# design4B.net
KiCad netlist of a schematic drawn in EAGLE
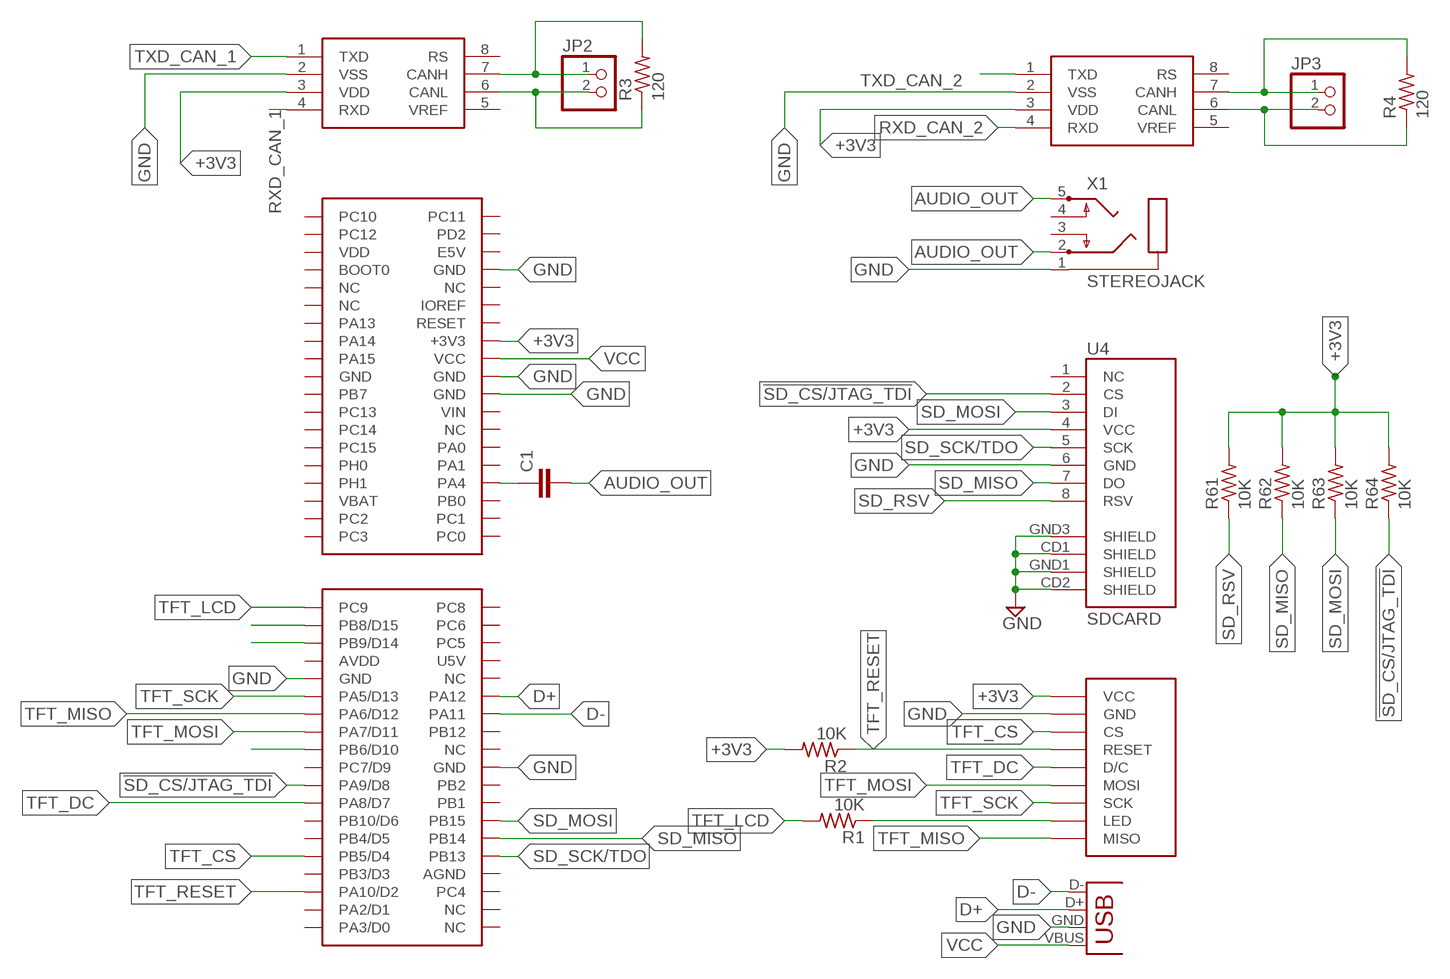
[diagram p0: schematic, sheet 1]

(export (version "E")
  (design (tool "Eeschema 10.0.6"))
  (components
    (comp (ref "C1")
      (value "CAP1206")
      (footprint "eagle-import:1206")
      (libsource (lib "eagle-import") (part "CAP1206"))
    )
    (comp (ref "J1")
      (value "SPI_TFT_DISPLAY")
      (footprint "eagle-import:SPI_DISPLAY")
      (libsource (lib "eagle-import") (part "SPI_TFT_DISPLAY"))
    )
    (comp (ref "JP1")
      (value "USB-A-H")
      (footprint "eagle-import:USB-A-H")
      (libsource (lib "eagle-import") (part "USB-A-H"))
    )
    (comp (ref "JP2")
      (value "HEADER-1X2")
      (footprint "eagle-import:1X02_OVAL")
      (libsource (lib "eagle-import") (part "HEADER-1X2"))
    )
    (comp (ref "JP3")
      (value "HEADER-1X2")
      (footprint "eagle-import:1X02_OVAL")
      (libsource (lib "eagle-import") (part "HEADER-1X2"))
    )
    (comp (ref "R1")
      (value "10K")
      (footprint "eagle-import:RLC_0603@1")
      (fields (field (name "MPN") "RMCF0603JT10K0"))
      (libsource (lib "eagle-import") (part "RESISTORRLC_0603"))
    )
    (comp (ref "R2")
      (value "10K")
      (footprint "eagle-import:RLC_0603@1")
      (fields (field (name "MPN") "RMCF0603JT10K0"))
      (libsource (lib "eagle-import") (part "RESISTORRLC_0603"))
    )
    (comp (ref "R3")
      (value "120")
      (footprint "eagle-import:RLC_0603@1")
      (fields (field (name "MPN") "RMCF0603JT10K0"))
      (libsource (lib "eagle-import") (part "RESISTORRLC_0603"))
    )
    (comp (ref "R4")
      (value "120")
      (footprint "eagle-import:RLC_0603@1")
      (fields (field (name "MPN") "RMCF0603JT10K0"))
      (libsource (lib "eagle-import") (part "RESISTORRLC_0603"))
    )
    (comp (ref "R61")
      (value "10K")
      (footprint "eagle-import:RLC_0603@1")
      (fields (field (name "MPN") "RMCF0603JT10K0"))
      (libsource (lib "eagle-import") (part "RESISTORRLC_0603"))
    )
    (comp (ref "R62")
      (value "10K")
      (footprint "eagle-import:RLC_0603@1")
      (fields (field (name "MPN") "RMCF0603JT10K0"))
      (libsource (lib "eagle-import") (part "RESISTORRLC_0603"))
    )
    (comp (ref "R63")
      (value "10K")
      (footprint "eagle-import:RLC_0603@1")
      (fields (field (name "MPN") "RMCF0603JT10K0"))
      (libsource (lib "eagle-import") (part "RESISTORRLC_0603"))
    )
    (comp (ref "R64")
      (value "10K")
      (footprint "eagle-import:RLC_0603@1")
      (fields (field (name "MPN") "RMCF0603JT10K0"))
      (libsource (lib "eagle-import") (part "RESISTORRLC_0603"))
    )
    (comp (ref "U$1")
      (value "MOPHOMOPHO_466RE")
      (footprint "eagle-import:MOPHO")
      (libsource (lib "eagle-import") (part "MOPHOMOPHO_466RE"))
    )
    (comp (ref "U1")
      (value "MCP2551")
      (footprint "eagle-import:SO08")
      (libsource (lib "eagle-import") (part "MCP2551"))
    )
    (comp (ref "U2")
      (value "MCP2551")
      (footprint "eagle-import:SO08")
      (libsource (lib "eagle-import") (part "MCP2551"))
    )
    (comp (ref "U4")
      (value "SDCARD")
      (footprint "eagle-import:MICRO-SD-SOCKET-PP")
      (libsource (lib "eagle-import") (part "USD-SOCKETNEW"))
    )
    (comp (ref "X1")
      (value "STEREOJACK")
      (footprint "eagle-import:STX3100")
      (libsource (lib "eagle-import") (part "STEREOJACK"))
    )
  )
  (nets
    (net (code "1") (name "+3V3") (class "Default")
      (node (ref "J1") (pin "VCC") (pinfunction "VCC_VCC") (pintype "power_in"))
      (node (ref "R2") (pin "2") (pinfunction "2_2") (pintype "passive"))
      (node (ref "R61") (pin "2") (pinfunction "2_2") (pintype "passive"))
      (node (ref "R62") (pin "2") (pinfunction "2_2") (pintype "passive"))
      (node (ref "R63") (pin "2") (pinfunction "2_2") (pintype "passive"))
      (node (ref "R64") (pin "2") (pinfunction "2_2") (pintype "passive"))
      (node (ref "U$1") (pin "P$16") (pinfunction "+3V3_P$16") (pintype "power_in"))
      (node (ref "U1") (pin "3") (pinfunction "VDD_3") (pintype "bidirectional"))
      (node (ref "U2") (pin "3") (pinfunction "VDD_3") (pintype "bidirectional"))
      (node (ref "U4") (pin "4") (pinfunction "VCC_4") (pintype "bidirectional"))
    )
    (net (code "2") (name "/AVDD") (class "Default")
      (node (ref "U$1") (pin "P$45") (pinfunction "AVDD_P$45") (pintype "power_in"))
    )
    (net (code "3") (name "/RXD_CAN_1") (class "Default")
      (node (ref "U2") (pin "4") (pinfunction "RXD_4") (pintype "bidirectional"))
    )
    (net (code "4") (name "/TXD_CAN_2") (class "Default")
      (node (ref "U1") (pin "1") (pinfunction "TXD_1") (pintype "bidirectional"))
    )
    (net (code "5") (name "/VBAT") (class "Default")
      (node (ref "U$1") (pin "P$33") (pinfunction "VBAT_P$33") (pintype "power_in"))
    )
    (net (code "6") (name "/VDD") (class "Default")
      (node (ref "U$1") (pin "P$5") (pinfunction "VDD_P$5") (pintype "power_in"))
    )
    (net (code "7") (name "/VIN") (class "Default")
      (node (ref "U$1") (pin "P$24") (pinfunction "VIN_P$24") (pintype "power_in"))
    )
    (net (code "8") (name "/~{SD_CS{slash}JTAG_TDI}") (class "Default")
      (node (ref "R64") (pin "1") (pinfunction "1_1") (pintype "passive"))
      (node (ref "U$1") (pin "P$59") (pinfunction "PA9/D8_P$59") (pintype "bidirectional"))
      (node (ref "U4") (pin "2") (pinfunction "CS_2") (pintype "bidirectional"))
    )
    (net (code "9") (name "AUDIO_OUT") (class "Default")
      (node (ref "C1") (pin "2") (pinfunction "2_2") (pintype "passive"))
      (node (ref "X1") (pin "2") (pinfunction "2_2") (pintype "passive"))
      (node (ref "X1") (pin "5") (pinfunction "5_5") (pintype "passive"))
    )
    (net (code "10") (name "D+") (class "Default")
      (node (ref "JP1") (pin "D+") (pinfunction "D-_D+") (pintype "bidirectional"))
      (node (ref "U$1") (pin "P$50") (pinfunction "PA12_P$50") (pintype "bidirectional"))
    )
    (net (code "11") (name "D-") (class "Default")
      (node (ref "JP1") (pin "D-") (pinfunction "D+_D-") (pintype "bidirectional"))
      (node (ref "U$1") (pin "P$52") (pinfunction "PA11_P$52") (pintype "bidirectional"))
    )
    (net (code "12") (name "GND") (class "Default")
      (node (ref "J1") (pin "GND") (pinfunction "GND_GND") (pintype "power_in"))
      (node (ref "JP1") (pin "GND") (pinfunction "VBUS_GND") (pintype "bidirectional"))
      (node (ref "U$1") (pin "P$20") (pinfunction "GND_P$20") (pintype "bidirectional"))
      (node (ref "U$1") (pin "P$22") (pinfunction "GND_P$22") (pintype "bidirectional"))
      (node (ref "U$1") (pin "P$47") (pinfunction "GND_P$47") (pintype "bidirectional"))
      (node (ref "U$1") (pin "P$58") (pinfunction "GND_P$58") (pintype "bidirectional"))
      (node (ref "U$1") (pin "P$8") (pinfunction "GND_P$8") (pintype "bidirectional"))
      (node (ref "U1") (pin "2") (pinfunction "VSS_2") (pintype "bidirectional"))
      (node (ref "U2") (pin "2") (pinfunction "VSS_2") (pintype "bidirectional"))
      (node (ref "U4") (pin "6") (pinfunction "GND_6") (pintype "bidirectional"))
      (node (ref "U4") (pin "CD1") (pinfunction "SHIELD_CD1") (pintype "bidirectional"))
      (node (ref "U4") (pin "CD2") (pinfunction "SHIELD_CD2") (pintype "bidirectional"))
      (node (ref "U4") (pin "GND1") (pinfunction "SHIELD_GND1") (pintype "bidirectional"))
      (node (ref "U4") (pin "GND3") (pinfunction "SHIELD_GND3") (pintype "bidirectional"))
      (node (ref "X1") (pin "1") (pinfunction "1_1") (pintype "passive"))
    )
    (net (code "13") (name "Net-(J1-PadLED)") (class "Default")
      (node (ref "J1") (pin "LED") (pinfunction "LED_LED") (pintype "bidirectional"))
      (node (ref "R1") (pin "1") (pinfunction "1_1") (pintype "passive"))
    )
    (net (code "14") (name "Net-(U$1-PA4)") (class "Default")
      (node (ref "C1") (pin "1") (pinfunction "1_1") (pintype "passive"))
      (node (ref "U$1") (pin "P$32") (pinfunction "PA4_P$32") (pintype "bidirectional"))
    )
    (net (code "15") (name "Net-(U1-CANH)") (class "Default")
      (node (ref "JP3") (pin "1") (pinfunction "1_1") (pintype "passive"))
      (node (ref "R4") (pin "2") (pinfunction "2_2") (pintype "passive"))
      (node (ref "U1") (pin "7") (pinfunction "CANH_7") (pintype "bidirectional"))
    )
    (net (code "16") (name "Net-(U1-CANL)") (class "Default")
      (node (ref "JP3") (pin "2") (pinfunction "2_2") (pintype "passive"))
      (node (ref "R4") (pin "1") (pinfunction "1_1") (pintype "passive"))
      (node (ref "U1") (pin "6") (pinfunction "CANL_6") (pintype "bidirectional"))
    )
    (net (code "17") (name "Net-(U2-CANH)") (class "Default")
      (node (ref "JP2") (pin "1") (pinfunction "1_1") (pintype "passive"))
      (node (ref "R3") (pin "2") (pinfunction "2_2") (pintype "passive"))
      (node (ref "U2") (pin "7") (pinfunction "CANH_7") (pintype "bidirectional"))
    )
    (net (code "18") (name "Net-(U2-CANL)") (class "Default")
      (node (ref "JP2") (pin "2") (pinfunction "2_2") (pintype "passive"))
      (node (ref "R3") (pin "1") (pinfunction "1_1") (pintype "passive"))
      (node (ref "U2") (pin "6") (pinfunction "CANL_6") (pintype "bidirectional"))
    )
    (net (code "19") (name "RXD_CAN_2") (class "Default")
      (node (ref "U1") (pin "4") (pinfunction "RXD_4") (pintype "bidirectional"))
    )
    (net (code "20") (name "SD_MISO") (class "Default")
      (node (ref "R62") (pin "1") (pinfunction "1_1") (pintype "passive"))
      (node (ref "U$1") (pin "P$66") (pinfunction "PB14_P$66") (pintype "bidirectional"))
      (node (ref "U4") (pin "7") (pinfunction "DO_7") (pintype "bidirectional"))
    )
    (net (code "21") (name "SD_MOSI") (class "Default")
      (node (ref "R63") (pin "1") (pinfunction "1_1") (pintype "passive"))
      (node (ref "U$1") (pin "P$64") (pinfunction "PB15_P$64") (pintype "bidirectional"))
      (node (ref "U4") (pin "3") (pinfunction "DI_3") (pintype "bidirectional"))
    )
    (net (code "22") (name "SD_RSV") (class "Default")
      (node (ref "R61") (pin "1") (pinfunction "1_1") (pintype "passive"))
      (node (ref "U4") (pin "8") (pinfunction "RSV_8") (pintype "bidirectional"))
    )
    (net (code "23") (name "SD_SCK{slash}TDO") (class "Default")
      (node (ref "U$1") (pin "P$68") (pinfunction "PB13_P$68") (pintype "bidirectional"))
      (node (ref "U4") (pin "5") (pinfunction "SCK_5") (pintype "bidirectional"))
    )
    (net (code "24") (name "TFT_CS") (class "Default")
      (node (ref "J1") (pin "CS") (pinfunction "CS_CS") (pintype "bidirectional"))
      (node (ref "U$1") (pin "P$67") (pinfunction "PB5/D4_P$67") (pintype "bidirectional"))
    )
    (net (code "25") (name "TFT_DC") (class "Default")
      (node (ref "J1") (pin "D/C") (pinfunction "D/C_D/C") (pintype "bidirectional"))
      (node (ref "U$1") (pin "P$61") (pinfunction "PA8/D7_P$61") (pintype "bidirectional"))
    )
    (net (code "26") (name "TFT_LCD") (class "Default")
      (node (ref "R1") (pin "2") (pinfunction "2_2") (pintype "passive"))
      (node (ref "U$1") (pin "P$39") (pinfunction "PC9_P$39") (pintype "bidirectional"))
    )
    (net (code "27") (name "TFT_MISO") (class "Default")
      (node (ref "J1") (pin "MISO") (pinfunction "MISO_MISO") (pintype "bidirectional"))
      (node (ref "U$1") (pin "P$51") (pinfunction "PA6/D12_P$51") (pintype "bidirectional"))
    )
    (net (code "28") (name "TFT_MOSI") (class "Default")
      (node (ref "J1") (pin "MOSI") (pinfunction "MOSI_MOSI") (pintype "bidirectional"))
      (node (ref "U$1") (pin "P$53") (pinfunction "PA7/D11_P$53") (pintype "bidirectional"))
    )
    (net (code "29") (name "TFT_RESET") (class "Default")
      (node (ref "J1") (pin "RESET") (pinfunction "RESET_RESET") (pintype "bidirectional"))
      (node (ref "R2") (pin "1") (pinfunction "1_1") (pintype "passive"))
      (node (ref "U$1") (pin "P$71") (pinfunction "PA10/D2_P$71") (pintype "bidirectional"))
    )
    (net (code "30") (name "TFT_SCK") (class "Default")
      (node (ref "J1") (pin "SCK") (pinfunction "SCK_SCK") (pintype "bidirectional"))
      (node (ref "U$1") (pin "P$49") (pinfunction "PA5/D13_P$49") (pintype "bidirectional"))
    )
    (net (code "31") (name "TXD_CAN_1") (class "Default")
      (node (ref "U2") (pin "1") (pinfunction "TXD_1") (pintype "bidirectional"))
    )
    (net (code "32") (name "VCC") (class "Default")
      (node (ref "JP1") (pin "VBUS") (pinfunction "GND_VBUS") (pintype "bidirectional"))
      (node (ref "U$1") (pin "P$18") (pinfunction "VCC_P$18") (pintype "power_in"))
    )
    (net (code "33") (name "unconnected-(U$1-AGND-PadP$70)") (class "Default")
      (node (ref "U$1") (pin "P$70") (pinfunction "AGND_P$70") (pintype "bidirectional"))
    )
    (net (code "34") (name "unconnected-(U$1-BOOT0-PadP$7)") (class "Default")
      (node (ref "U$1") (pin "P$7") (pinfunction "BOOT0_P$7") (pintype "bidirectional"))
    )
    (net (code "35") (name "unconnected-(U$1-E5V-PadP$6)") (class "Default")
      (node (ref "U$1") (pin "P$6") (pinfunction "E5V_P$6") (pintype "bidirectional"))
    )
    (net (code "36") (name "unconnected-(U$1-GND-PadP$19)") (class "Default")
      (node (ref "U$1") (pin "P$19") (pinfunction "GND_P$19") (pintype "bidirectional"))
    )
    (net (code "37") (name "unconnected-(U$1-IOREF-PadP$12)") (class "Default")
      (node (ref "U$1") (pin "P$12") (pinfunction "IOREF_P$12") (pintype "bidirectional"))
    )
    (net (code "38") (name "unconnected-(U$1-NC-PadP$9)") (class "Default")
      (node (ref "U$1") (pin "P$9") (pinfunction "NC_P$9") (pintype "bidirectional"))
    )
    (net (code "39") (name "unconnected-(U$1-NC-PadP$10)") (class "Default")
      (node (ref "U$1") (pin "P$10") (pinfunction "NC_P$10") (pintype "bidirectional"))
    )
    (net (code "40") (name "unconnected-(U$1-NC-PadP$11)") (class "Default")
      (node (ref "U$1") (pin "P$11") (pinfunction "NC_P$11") (pintype "bidirectional"))
    )
    (net (code "41") (name "unconnected-(U$1-NC-PadP$26)") (class "Default")
      (node (ref "U$1") (pin "P$26") (pinfunction "NC_P$26") (pintype "bidirectional"))
    )
    (net (code "42") (name "unconnected-(U$1-NC-PadP$48)") (class "Default")
      (node (ref "U$1") (pin "P$48") (pinfunction "NC_P$48") (pintype "bidirectional"))
    )
    (net (code "43") (name "unconnected-(U$1-NC-PadP$56)") (class "Default")
      (node (ref "U$1") (pin "P$56") (pinfunction "NC_P$56") (pintype "bidirectional"))
    )
    (net (code "44") (name "unconnected-(U$1-NC-PadP$74)") (class "Default")
      (node (ref "U$1") (pin "P$74") (pinfunction "NC_P$74") (pintype "bidirectional"))
    )
    (net (code "45") (name "unconnected-(U$1-NC-PadP$76)") (class "Default")
      (node (ref "U$1") (pin "P$76") (pinfunction "NC_P$76") (pintype "bidirectional"))
    )
    (net (code "46") (name "unconnected-(U$1-PA0-PadP$28)") (class "Default")
      (node (ref "U$1") (pin "P$28") (pinfunction "PA0_P$28") (pintype "bidirectional"))
    )
    (net (code "47") (name "unconnected-(U$1-PA1-PadP$30)") (class "Default")
      (node (ref "U$1") (pin "P$30") (pinfunction "PA1_P$30") (pintype "bidirectional"))
    )
    (net (code "48") (name "unconnected-(U$1-PA2{slash}D1-PadP$73)") (class "Default")
      (node (ref "U$1") (pin "P$73") (pinfunction "PA2/D1_P$73") (pintype "bidirectional"))
    )
    (net (code "49") (name "unconnected-(U$1-PA3{slash}D0-PadP$75)") (class "Default")
      (node (ref "U$1") (pin "P$75") (pinfunction "PA3/D0_P$75") (pintype "bidirectional"))
    )
    (net (code "50") (name "unconnected-(U$1-PA13-PadP$13)") (class "Default")
      (node (ref "U$1") (pin "P$13") (pinfunction "PA13_P$13") (pintype "bidirectional"))
    )
    (net (code "51") (name "unconnected-(U$1-PA14-PadP$15)") (class "Default")
      (node (ref "U$1") (pin "P$15") (pinfunction "PA14_P$15") (pintype "bidirectional"))
    )
    (net (code "52") (name "unconnected-(U$1-PA15-PadP$17)") (class "Default")
      (node (ref "U$1") (pin "P$17") (pinfunction "PA15_P$17") (pintype "bidirectional"))
    )
    (net (code "53") (name "unconnected-(U$1-PB0-PadP$34)") (class "Default")
      (node (ref "U$1") (pin "P$34") (pinfunction "PB0_P$34") (pintype "bidirectional"))
    )
    (net (code "54") (name "unconnected-(U$1-PB1-PadP$62)") (class "Default")
      (node (ref "U$1") (pin "P$62") (pinfunction "PB1_P$62") (pintype "bidirectional"))
    )
    (net (code "55") (name "unconnected-(U$1-PB2-PadP$60)") (class "Default")
      (node (ref "U$1") (pin "P$60") (pinfunction "PB2_P$60") (pintype "bidirectional"))
    )
    (net (code "56") (name "unconnected-(U$1-PB3{slash}D3-PadP$69)") (class "Default")
      (node (ref "U$1") (pin "P$69") (pinfunction "PB3/D3_P$69") (pintype "bidirectional"))
    )
    (net (code "57") (name "unconnected-(U$1-PB4{slash}D5-PadP$65)") (class "Default")
      (node (ref "U$1") (pin "P$65") (pinfunction "PB4/D5_P$65") (pintype "bidirectional"))
    )
    (net (code "58") (name "unconnected-(U$1-PB6{slash}D10-PadP$55)") (class "Default")
      (node (ref "U$1") (pin "P$55") (pinfunction "PB6/D10_P$55") (pintype "bidirectional"))
    )
    (net (code "59") (name "unconnected-(U$1-PB7-PadP$21)") (class "Default")
      (node (ref "U$1") (pin "P$21") (pinfunction "PB7_P$21") (pintype "bidirectional"))
    )
    (net (code "60") (name "unconnected-(U$1-PB8{slash}D15-PadP$41)") (class "Default")
      (node (ref "U$1") (pin "P$41") (pinfunction "PB8/D15_P$41") (pintype "bidirectional"))
    )
    (net (code "61") (name "unconnected-(U$1-PB9{slash}D14-PadP$43)") (class "Default")
      (node (ref "U$1") (pin "P$43") (pinfunction "PB9/D14_P$43") (pintype "bidirectional"))
    )
    (net (code "62") (name "unconnected-(U$1-PB10{slash}D6-PadP$63)") (class "Default")
      (node (ref "U$1") (pin "P$63") (pinfunction "PB10/D6_P$63") (pintype "bidirectional"))
    )
    (net (code "63") (name "unconnected-(U$1-PB12-PadP$54)") (class "Default")
      (node (ref "U$1") (pin "P$54") (pinfunction "PB12_P$54") (pintype "bidirectional"))
    )
    (net (code "64") (name "unconnected-(U$1-PC0-PadP$38)") (class "Default")
      (node (ref "U$1") (pin "P$38") (pinfunction "PC0_P$38") (pintype "bidirectional"))
    )
    (net (code "65") (name "unconnected-(U$1-PC1-PadP$36)") (class "Default")
      (node (ref "U$1") (pin "P$36") (pinfunction "PC1_P$36") (pintype "bidirectional"))
    )
    (net (code "66") (name "unconnected-(U$1-PC2-PadP$35)") (class "Default")
      (node (ref "U$1") (pin "P$35") (pinfunction "PC2_P$35") (pintype "bidirectional"))
    )
    (net (code "67") (name "unconnected-(U$1-PC3-PadP$37)") (class "Default")
      (node (ref "U$1") (pin "P$37") (pinfunction "PC3_P$37") (pintype "bidirectional"))
    )
    (net (code "68") (name "unconnected-(U$1-PC4-PadP$72)") (class "Default")
      (node (ref "U$1") (pin "P$72") (pinfunction "PC4_P$72") (pintype "bidirectional"))
    )
    (net (code "69") (name "unconnected-(U$1-PC5-PadP$44)") (class "Default")
      (node (ref "U$1") (pin "P$44") (pinfunction "PC5_P$44") (pintype "bidirectional"))
    )
    (net (code "70") (name "unconnected-(U$1-PC6-PadP$42)") (class "Default")
      (node (ref "U$1") (pin "P$42") (pinfunction "PC6_P$42") (pintype "bidirectional"))
    )
    (net (code "71") (name "unconnected-(U$1-PC7{slash}D9-PadP$57)") (class "Default")
      (node (ref "U$1") (pin "P$57") (pinfunction "PC7/D9_P$57") (pintype "bidirectional"))
    )
    (net (code "72") (name "unconnected-(U$1-PC8-PadP$40)") (class "Default")
      (node (ref "U$1") (pin "P$40") (pinfunction "PC8_P$40") (pintype "bidirectional"))
    )
    (net (code "73") (name "unconnected-(U$1-PC10-PadP$1)") (class "Default")
      (node (ref "U$1") (pin "P$1") (pinfunction "PC10_P$1") (pintype "bidirectional"))
    )
    (net (code "74") (name "unconnected-(U$1-PC11-PadP$2)") (class "Default")
      (node (ref "U$1") (pin "P$2") (pinfunction "PC11_P$2") (pintype "bidirectional"))
    )
    (net (code "75") (name "unconnected-(U$1-PC12-PadP$3)") (class "Default")
      (node (ref "U$1") (pin "P$3") (pinfunction "PC12_P$3") (pintype "bidirectional"))
    )
    (net (code "76") (name "unconnected-(U$1-PC13-PadP$23)") (class "Default")
      (node (ref "U$1") (pin "P$23") (pinfunction "PC13_P$23") (pintype "bidirectional"))
    )
    (net (code "77") (name "unconnected-(U$1-PC14-PadP$25)") (class "Default")
      (node (ref "U$1") (pin "P$25") (pinfunction "PC14_P$25") (pintype "bidirectional"))
    )
    (net (code "78") (name "unconnected-(U$1-PC15-PadP$27)") (class "Default")
      (node (ref "U$1") (pin "P$27") (pinfunction "PC15_P$27") (pintype "bidirectional"))
    )
    (net (code "79") (name "unconnected-(U$1-PD2-PadP$4)") (class "Default")
      (node (ref "U$1") (pin "P$4") (pinfunction "PD2_P$4") (pintype "bidirectional"))
    )
    (net (code "80") (name "unconnected-(U$1-PH0-PadP$29)") (class "Default")
      (node (ref "U$1") (pin "P$29") (pinfunction "PH0_P$29") (pintype "bidirectional"))
    )
    (net (code "81") (name "unconnected-(U$1-PH1-PadP$31)") (class "Default")
      (node (ref "U$1") (pin "P$31") (pinfunction "PH1_P$31") (pintype "bidirectional"))
    )
    (net (code "82") (name "unconnected-(U$1-RESET-PadP$14)") (class "Default")
      (node (ref "U$1") (pin "P$14") (pinfunction "RESET_P$14") (pintype "bidirectional"))
    )
    (net (code "83") (name "unconnected-(U$1-U5V-PadP$46)") (class "Default")
      (node (ref "U$1") (pin "P$46") (pinfunction "U5V_P$46") (pintype "bidirectional"))
    )
    (net (code "84") (name "unconnected-(U1-RS-Pad8)") (class "Default")
      (node (ref "U1") (pin "8") (pinfunction "RS_8") (pintype "bidirectional"))
    )
    (net (code "85") (name "unconnected-(U1-VREF-Pad5)") (class "Default")
      (node (ref "U1") (pin "5") (pinfunction "VREF_5") (pintype "bidirectional"))
    )
    (net (code "86") (name "unconnected-(U2-RS-Pad8)") (class "Default")
      (node (ref "U2") (pin "8") (pinfunction "RS_8") (pintype "bidirectional"))
    )
    (net (code "87") (name "unconnected-(U2-VREF-Pad5)") (class "Default")
      (node (ref "U2") (pin "5") (pinfunction "VREF_5") (pintype "bidirectional"))
    )
    (net (code "88") (name "unconnected-(U4-NC-Pad1)") (class "Default")
      (node (ref "U4") (pin "1") (pinfunction "NC_1") (pintype "bidirectional"))
    )
    (net (code "89") (name "unconnected-(X1-Pad3)") (class "Default")
      (node (ref "X1") (pin "3") (pinfunction "3_3") (pintype "passive"))
    )
    (net (code "90") (name "unconnected-(X1-Pad4)") (class "Default")
      (node (ref "X1") (pin "4") (pinfunction "4_4") (pintype "passive"))
    )
  )
)
